# stackable_motorshield_v2.net
KiCad netlist of a schematic drawn in EAGLE
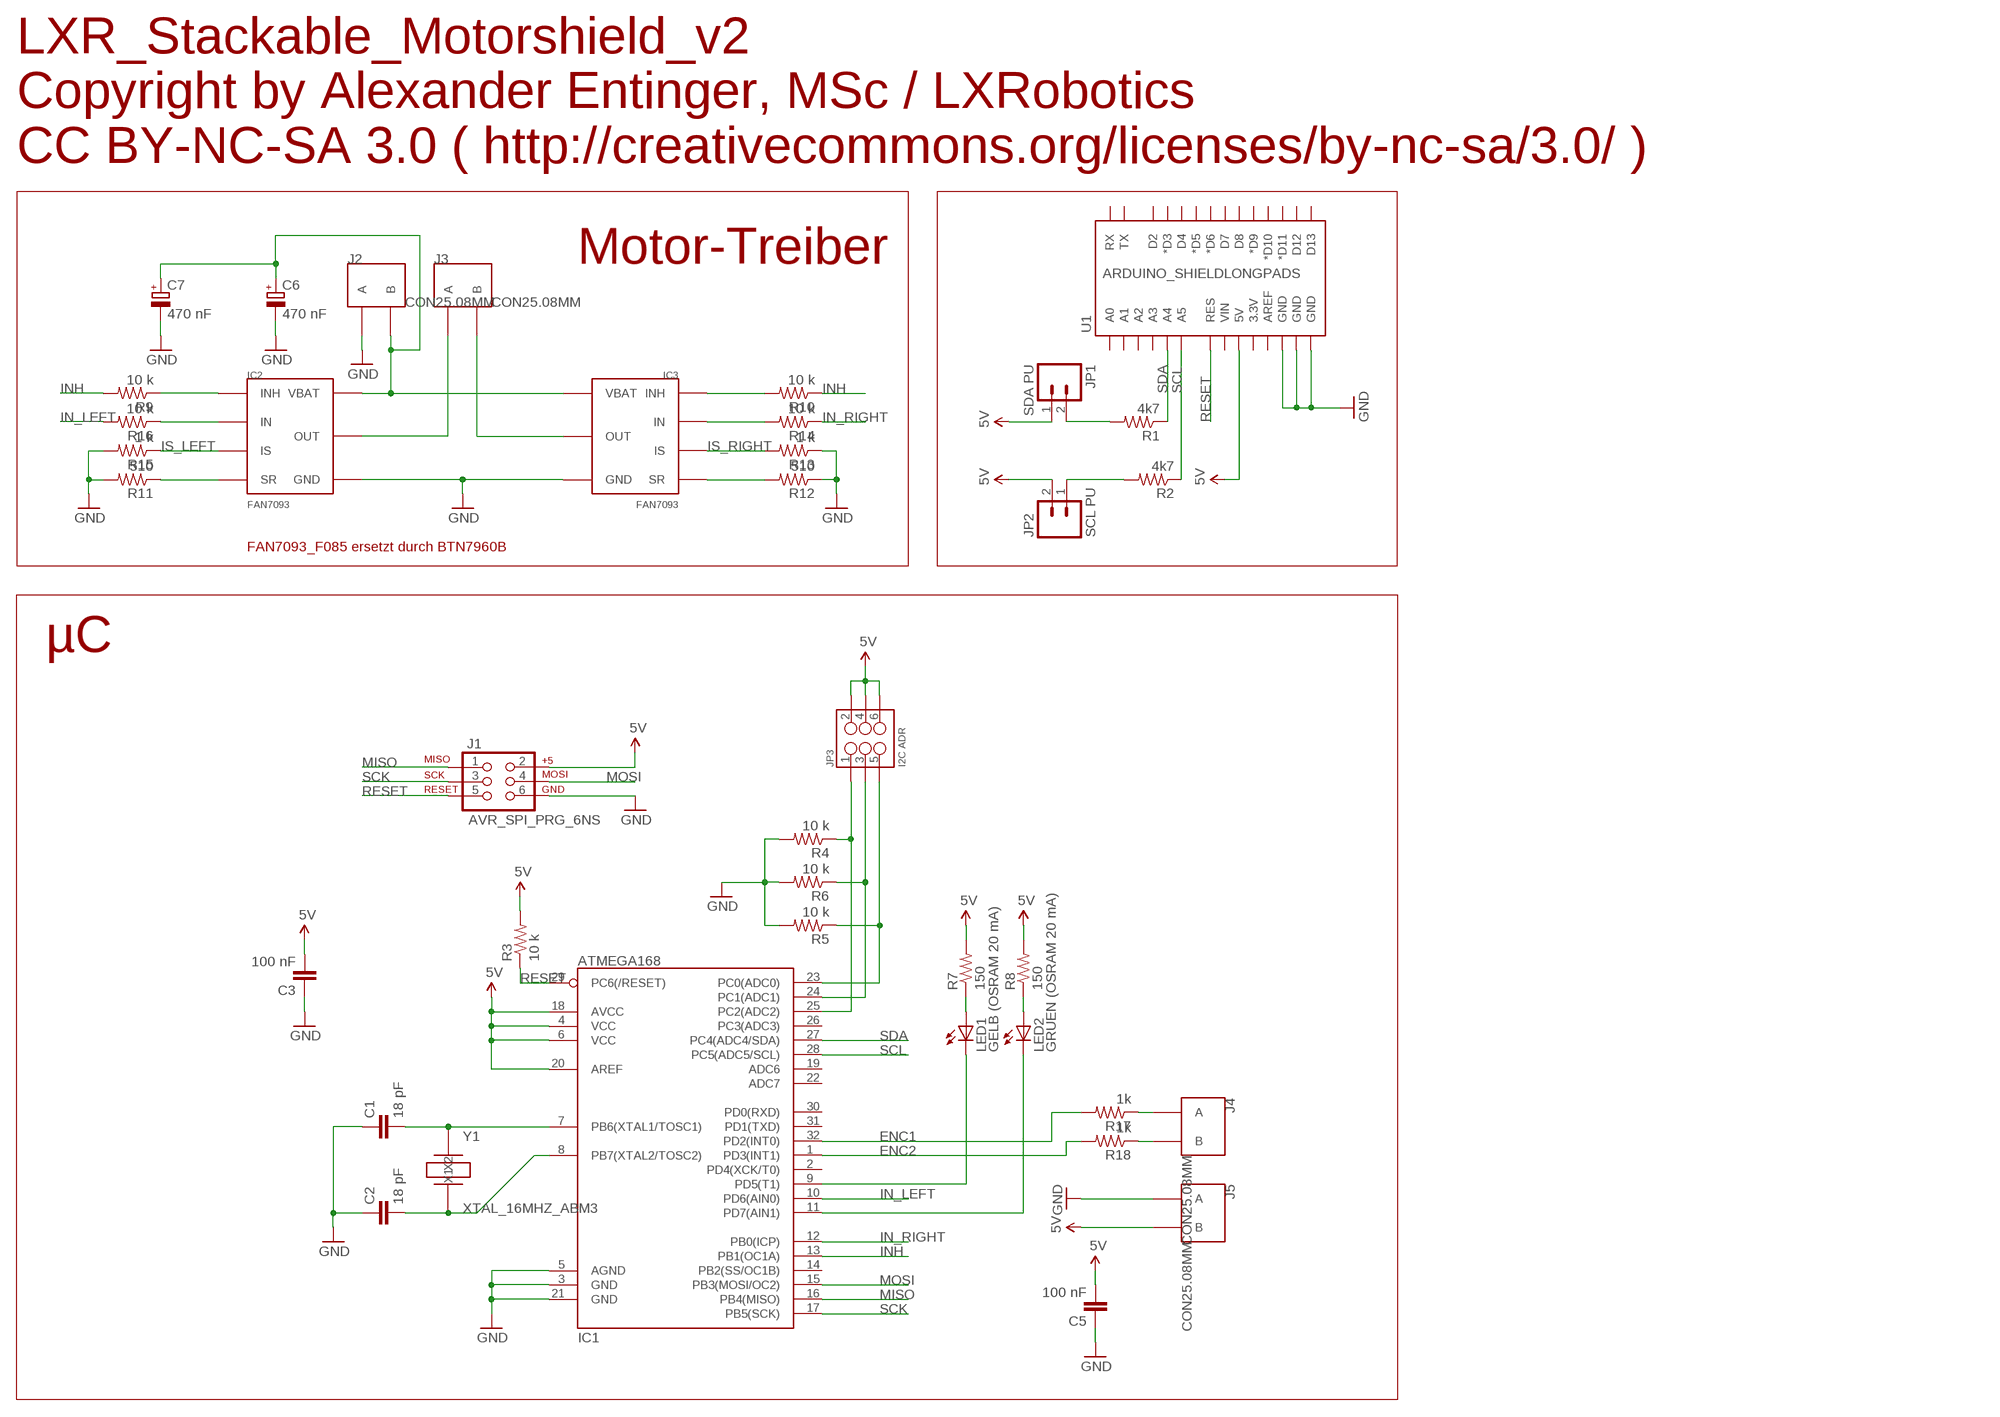
[diagram p0: schematic, sheet 1]

(export (version "E")
  (design (tool "Eeschema 10.0.6"))
  (components
    (comp (ref "C1")
      (value "18 pF")
      (footprint "eagle-import:C0805")
      (libsource (lib "eagle-import") (part "C-EUC0805"))
    )
    (comp (ref "C2")
      (value "18 pF")
      (footprint "eagle-import:C0805")
      (libsource (lib "eagle-import") (part "C-EUC0805"))
    )
    (comp (ref "C3")
      (value "100 nF")
      (footprint "eagle-import:C0805")
      (libsource (lib "eagle-import") (part "C-EUC0805"))
    )
    (comp (ref "C5")
      (value "100 nF")
      (footprint "eagle-import:C0805")
      (libsource (lib "eagle-import") (part "C-EUC0805"))
    )
    (comp (ref "C6")
      (value "470 nF")
      (footprint "eagle-import:KEMET_A")
      (libsource (lib "eagle-import") (part "CPOL-EU"))
    )
    (comp (ref "C7")
      (value "470 nF")
      (footprint "eagle-import:KEMET_A")
      (libsource (lib "eagle-import") (part "CPOL-EU"))
    )
    (comp (ref "IC1")
      (value "ATMEGA168")
      (footprint "eagle-import:TQFP32-08")
      (libsource (lib "eagle-import") (part "ATMEGA168"))
    )
    (comp (ref "IC2")
      (value "FAN7093")
      (footprint "eagle-import:TO263-7L")
      (libsource (lib "eagle-import") (part "FAN7093"))
    )
    (comp (ref "IC3")
      (value "FAN7093")
      (footprint "eagle-import:TO263-7L")
      (libsource (lib "eagle-import") (part "FAN7093"))
    )
    (comp (ref "J1")
      (value "AVR_SPI_PRG_6NS")
      (footprint "eagle-import:2X3-NS")
      (libsource (lib "eagle-import") (part "AVR_SPI_PRG_6NS"))
    )
    (comp (ref "J2")
      (value "CON25.08MM")
      (footprint "eagle-import:CON2_SCHRAUBKLEMME")
      (libsource (lib "eagle-import") (part "CON25.08MM"))
    )
    (comp (ref "J3")
      (value "CON25.08MM")
      (footprint "eagle-import:CON2_SCHRAUBKLEMME")
      (libsource (lib "eagle-import") (part "CON25.08MM"))
    )
    (comp (ref "J4")
      (value "CON25.08MM")
      (footprint "eagle-import:CON2_SCHRAUBKLEMME")
      (libsource (lib "eagle-import") (part "CON25.08MM"))
    )
    (comp (ref "J5")
      (value "CON25.08MM")
      (footprint "eagle-import:CON2_SCHRAUBKLEMME")
      (libsource (lib "eagle-import") (part "CON25.08MM"))
    )
    (comp (ref "JP1")
      (value "SDA PU")
      (footprint "eagle-import:1X02")
      (libsource (lib "eagle-import") (part "M02PTH"))
    )
    (comp (ref "JP2")
      (value "SCL PU")
      (footprint "eagle-import:1X02")
      (libsource (lib "eagle-import") (part "M02PTH"))
    )
    (comp (ref "JP3")
      (value "I2C ADR")
      (footprint "eagle-import:2X3_POGO")
      (libsource (lib "eagle-import") (part "M03X2POGO_PINS"))
    )
    (comp (ref "LED1")
      (value "GELB (OSRAM 20 mA)")
      (footprint "eagle-import:CHIP-LED0805")
      (libsource (lib "eagle-import") (part "LEDCHIP-LED0805"))
    )
    (comp (ref "LED2")
      (value "GRUEN (OSRAM 20 mA)")
      (footprint "eagle-import:CHIP-LED0805")
      (libsource (lib "eagle-import") (part "LEDCHIP-LED0805"))
    )
    (comp (ref "R1")
      (value "4k7")
      (footprint "eagle-import:0805")
      (libsource (lib "eagle-import") (part "RESISTOR0805-RES"))
    )
    (comp (ref "R2")
      (value "4k7")
      (footprint "eagle-import:0805")
      (libsource (lib "eagle-import") (part "RESISTOR0805-RES"))
    )
    (comp (ref "R3")
      (value "10 k")
      (footprint "eagle-import:0805")
      (libsource (lib "eagle-import") (part "RESISTOR0805-RES"))
    )
    (comp (ref "R4")
      (value "10 k")
      (footprint "eagle-import:0805")
      (libsource (lib "eagle-import") (part "RESISTOR0805-RES"))
    )
    (comp (ref "R5")
      (value "10 k")
      (footprint "eagle-import:0805")
      (libsource (lib "eagle-import") (part "RESISTOR0805-RES"))
    )
    (comp (ref "R6")
      (value "10 k")
      (footprint "eagle-import:0805")
      (libsource (lib "eagle-import") (part "RESISTOR0805-RES"))
    )
    (comp (ref "R7")
      (value "150")
      (footprint "eagle-import:0805")
      (libsource (lib "eagle-import") (part "RESISTOR0805-RES"))
    )
    (comp (ref "R8")
      (value "150")
      (footprint "eagle-import:0805")
      (libsource (lib "eagle-import") (part "RESISTOR0805-RES"))
    )
    (comp (ref "R9")
      (value "10 k")
      (footprint "eagle-import:0805")
      (libsource (lib "eagle-import") (part "RESISTOR0805-RES"))
    )
    (comp (ref "R10")
      (value "10 k")
      (footprint "eagle-import:0805")
      (libsource (lib "eagle-import") (part "RESISTOR0805-RES"))
    )
    (comp (ref "R11")
      (value "510")
      (footprint "eagle-import:0805")
      (libsource (lib "eagle-import") (part "RESISTOR0805-RES"))
    )
    (comp (ref "R12")
      (value "510")
      (footprint "eagle-import:0805")
      (libsource (lib "eagle-import") (part "RESISTOR0805-RES"))
    )
    (comp (ref "R13")
      (value "1 k")
      (footprint "eagle-import:0805")
      (libsource (lib "eagle-import") (part "RESISTOR0805-RES"))
    )
    (comp (ref "R14")
      (value "10 k")
      (footprint "eagle-import:0805")
      (libsource (lib "eagle-import") (part "RESISTOR0805-RES"))
    )
    (comp (ref "R15")
      (value "1 k")
      (footprint "eagle-import:0805")
      (libsource (lib "eagle-import") (part "RESISTOR0805-RES"))
    )
    (comp (ref "R16")
      (value "10 k")
      (footprint "eagle-import:0805")
      (libsource (lib "eagle-import") (part "RESISTOR0805-RES"))
    )
    (comp (ref "R17")
      (value "1k")
      (footprint "eagle-import:0805")
      (libsource (lib "eagle-import") (part "RESISTOR0805-RES"))
    )
    (comp (ref "R18")
      (value "1k")
      (footprint "eagle-import:0805")
      (libsource (lib "eagle-import") (part "RESISTOR0805-RES"))
    )
    (comp (ref "U1")
      (value "ARDUINO_SHIELDLONGPADS")
      (footprint "eagle-import:DUEMILANOVE_SHIELD_LONGPADS")
      (libsource (lib "eagle-import") (part "ARDUINO_SHIELDLONGPADS"))
    )
    (comp (ref "Y1")
      (value "XTAL_16MHZ_ABM3")
      (footprint "eagle-import:ABM3")
      (libsource (lib "eagle-import") (part "XTAL_16MHZ_ABM3"))
    )
  )
  (nets
    (net (code "1") (name "/ENC1") (class "Default")
      (node (ref "IC1") (pin "32") (pinfunction "PD2(INT0)_32") (pintype "bidirectional"))
      (node (ref "R17") (pin "2") (pinfunction "2_2") (pintype "passive"))
    )
    (net (code "2") (name "/ENC2") (class "Default")
      (node (ref "IC1") (pin "1") (pinfunction "PD3(INT1)_1") (pintype "bidirectional"))
      (node (ref "R18") (pin "2") (pinfunction "2_2") (pintype "passive"))
    )
    (net (code "3") (name "/INH") (class "Default")
      (node (ref "IC1") (pin "13") (pinfunction "PB1(OC1A)_13") (pintype "bidirectional"))
      (node (ref "R10") (pin "1") (pinfunction "1_1") (pintype "passive"))
      (node (ref "R9") (pin "2") (pinfunction "2_2") (pintype "passive"))
    )
    (net (code "4") (name "/IN_LEFT") (class "Default")
      (node (ref "IC1") (pin "10") (pinfunction "PD6(AIN0)_10") (pintype "bidirectional"))
      (node (ref "R16") (pin "2") (pinfunction "2_2") (pintype "passive"))
    )
    (net (code "5") (name "/IN_RIGHT") (class "Default")
      (node (ref "IC1") (pin "12") (pinfunction "PB0(ICP)_12") (pintype "bidirectional"))
      (node (ref "R14") (pin "1") (pinfunction "1_1") (pintype "passive"))
    )
    (net (code "6") (name "/IS_LEFT") (class "Default")
      (node (ref "IC2") (pin "IS") (pinfunction "IS_IS") (pintype "bidirectional"))
      (node (ref "R15") (pin "1") (pinfunction "1_1") (pintype "passive"))
    )
    (net (code "7") (name "/IS_RIGHT") (class "Default")
      (node (ref "IC3") (pin "IS") (pinfunction "IS_IS") (pintype "bidirectional"))
      (node (ref "R13") (pin "2") (pinfunction "2_2") (pintype "passive"))
    )
    (net (code "8") (name "/MISO") (class "Default")
      (node (ref "IC1") (pin "16") (pinfunction "PB4(MISO)_16") (pintype "bidirectional"))
      (node (ref "J1") (pin "1") (pinfunction "1_1") (pintype "passive"))
    )
    (net (code "9") (name "/MOSI") (class "Default")
      (node (ref "IC1") (pin "15") (pinfunction "PB3(MOSI/OC2)_15") (pintype "bidirectional"))
      (node (ref "J1") (pin "4") (pinfunction "4_4") (pintype "passive"))
    )
    (net (code "10") (name "/RESET") (class "Default")
      (node (ref "IC1") (pin "29") (pinfunction "PC6(/RESET)_29") (pintype "bidirectional"))
      (node (ref "J1") (pin "5") (pinfunction "5_5") (pintype "passive"))
      (node (ref "R3") (pin "1") (pinfunction "1_1") (pintype "passive"))
      (node (ref "U1") (pin "RES") (pinfunction "RES_RES") (pintype "bidirectional"))
    )
    (net (code "11") (name "/SCK") (class "Default")
      (node (ref "IC1") (pin "17") (pinfunction "PB5(SCK)_17") (pintype "bidirectional"))
      (node (ref "J1") (pin "3") (pinfunction "3_3") (pintype "passive"))
    )
    (net (code "12") (name "/SCL") (class "Default")
      (node (ref "IC1") (pin "28") (pinfunction "PC5(ADC5/SCL)_28") (pintype "bidirectional"))
      (node (ref "R2") (pin "1") (pinfunction "1_1") (pintype "passive"))
      (node (ref "U1") (pin "A5") (pinfunction "A5_A5") (pintype "bidirectional"))
    )
    (net (code "13") (name "/SDA") (class "Default")
      (node (ref "IC1") (pin "27") (pinfunction "PC4(ADC4/SDA)_27") (pintype "bidirectional"))
      (node (ref "R1") (pin "1") (pinfunction "1_1") (pintype "passive"))
      (node (ref "U1") (pin "A4") (pinfunction "A4_A4") (pintype "bidirectional"))
    )
    (net (code "14") (name "5V") (class "Default")
      (node (ref "C3") (pin "2") (pinfunction "2_2") (pintype "passive"))
      (node (ref "C5") (pin "2") (pinfunction "2_2") (pintype "passive"))
      (node (ref "IC1") (pin "18") (pinfunction "AVCC_18") (pintype "bidirectional"))
      (node (ref "IC1") (pin "20") (pinfunction "AREF_20") (pintype "bidirectional"))
      (node (ref "IC1") (pin "4") (pinfunction "VCC_4") (pintype "bidirectional"))
      (node (ref "IC1") (pin "6") (pinfunction "VCC_6") (pintype "bidirectional"))
      (node (ref "J1") (pin "2") (pinfunction "2_2") (pintype "passive"))
      (node (ref "J5") (pin "2") (pinfunction "B_2") (pintype "bidirectional"))
      (node (ref "JP1") (pin "1") (pinfunction "1_1") (pintype "passive"))
      (node (ref "JP2") (pin "2") (pinfunction "2_2") (pintype "passive"))
      (node (ref "JP3") (pin "P$2") (pinfunction "2_P$2") (pintype "bidirectional"))
      (node (ref "JP3") (pin "P$4") (pinfunction "4_P$4") (pintype "bidirectional"))
      (node (ref "JP3") (pin "P$6") (pinfunction "6_P$6") (pintype "bidirectional"))
      (node (ref "R3") (pin "2") (pinfunction "2_2") (pintype "passive"))
      (node (ref "R7") (pin "2") (pinfunction "2_2") (pintype "passive"))
      (node (ref "R8") (pin "2") (pinfunction "2_2") (pintype "passive"))
      (node (ref "U1") (pin "5V") (pinfunction "5V_5V") (pintype "bidirectional"))
    )
    (net (code "15") (name "GND") (class "Default")
      (node (ref "C1") (pin "1") (pinfunction "1_1") (pintype "passive"))
      (node (ref "C2") (pin "1") (pinfunction "1_1") (pintype "passive"))
      (node (ref "C3") (pin "1") (pinfunction "1_1") (pintype "passive"))
      (node (ref "C5") (pin "1") (pinfunction "1_1") (pintype "passive"))
      (node (ref "C6") (pin "CATHODE") (pinfunction "-_CATHODE") (pintype "passive"))
      (node (ref "C7") (pin "CATHODE") (pinfunction "-_CATHODE") (pintype "passive"))
      (node (ref "IC1") (pin "21") (pinfunction "GND_21") (pintype "bidirectional"))
      (node (ref "IC1") (pin "3") (pinfunction "GND_3") (pintype "bidirectional"))
      (node (ref "IC1") (pin "5") (pinfunction "AGND_5") (pintype "bidirectional"))
      (node (ref "IC2") (pin "GND") (pinfunction "GND_GND") (pintype "bidirectional"))
      (node (ref "IC3") (pin "GND") (pinfunction "GND_GND") (pintype "bidirectional"))
      (node (ref "J1") (pin "6") (pinfunction "6_6") (pintype "passive"))
      (node (ref "J2") (pin "1") (pinfunction "A_1") (pintype "bidirectional"))
      (node (ref "J5") (pin "1") (pinfunction "A_1") (pintype "bidirectional"))
      (node (ref "R11") (pin "2") (pinfunction "2_2") (pintype "passive"))
      (node (ref "R12") (pin "1") (pinfunction "1_1") (pintype "passive"))
      (node (ref "R13") (pin "1") (pinfunction "1_1") (pintype "passive"))
      (node (ref "R15") (pin "2") (pinfunction "2_2") (pintype "passive"))
      (node (ref "R4") (pin "2") (pinfunction "2_2") (pintype "passive"))
      (node (ref "R5") (pin "2") (pinfunction "2_2") (pintype "passive"))
      (node (ref "R6") (pin "2") (pinfunction "2_2") (pintype "passive"))
      (node (ref "U1") (pin "GND@0") (pinfunction "GND_GND@0") (pintype "bidirectional"))
      (node (ref "U1") (pin "GND@1") (pinfunction "GND_GND@1") (pintype "bidirectional"))
      (node (ref "U1") (pin "GND@2") (pinfunction "GND_GND@2") (pintype "bidirectional"))
    )
    (net (code "16") (name "Net-(C6-+)") (class "Default")
      (node (ref "C6") (pin "ANODE") (pinfunction "+_ANODE") (pintype "passive"))
      (node (ref "C7") (pin "ANODE") (pinfunction "+_ANODE") (pintype "passive"))
      (node (ref "IC2") (pin "VBATT") (pinfunction "VBAT_VBATT") (pintype "bidirectional"))
      (node (ref "IC3") (pin "VBATT") (pinfunction "VBAT_VBATT") (pintype "bidirectional"))
      (node (ref "J2") (pin "2") (pinfunction "B_2") (pintype "bidirectional"))
    )
    (net (code "17") (name "Net-(IC1-PB6(XTAL1{slash}TOSC1))") (class "Default")
      (node (ref "C1") (pin "2") (pinfunction "2_2") (pintype "passive"))
      (node (ref "IC1") (pin "7") (pinfunction "PB6(XTAL1/TOSC1)_7") (pintype "bidirectional"))
      (node (ref "Y1") (pin "X1") (pinfunction "X1_X1") (pintype "bidirectional"))
    )
    (net (code "18") (name "Net-(IC1-PB7(XTAL2{slash}TOSC2))") (class "Default")
      (node (ref "C2") (pin "2") (pinfunction "2_2") (pintype "passive"))
      (node (ref "IC1") (pin "8") (pinfunction "PB7(XTAL2/TOSC2)_8") (pintype "bidirectional"))
      (node (ref "Y1") (pin "X2") (pinfunction "X2_X2") (pintype "bidirectional"))
    )
    (net (code "19") (name "Net-(IC1-PC0(ADC0))") (class "Default")
      (node (ref "IC1") (pin "23") (pinfunction "PC0(ADC0)_23") (pintype "bidirectional"))
      (node (ref "JP3") (pin "P$5") (pinfunction "5_P$5") (pintype "bidirectional"))
      (node (ref "R5") (pin "1") (pinfunction "1_1") (pintype "passive"))
    )
    (net (code "20") (name "Net-(IC1-PC1(ADC1))") (class "Default")
      (node (ref "IC1") (pin "24") (pinfunction "PC1(ADC1)_24") (pintype "bidirectional"))
      (node (ref "JP3") (pin "P$3") (pinfunction "3_P$3") (pintype "bidirectional"))
      (node (ref "R6") (pin "1") (pinfunction "1_1") (pintype "passive"))
    )
    (net (code "21") (name "Net-(IC1-PC2(ADC2))") (class "Default")
      (node (ref "IC1") (pin "25") (pinfunction "PC2(ADC2)_25") (pintype "bidirectional"))
      (node (ref "JP3") (pin "P$1") (pinfunction "1_P$1") (pintype "bidirectional"))
      (node (ref "R4") (pin "1") (pinfunction "1_1") (pintype "passive"))
    )
    (net (code "22") (name "Net-(IC1-PD5(T1))") (class "Default")
      (node (ref "IC1") (pin "9") (pinfunction "PD5(T1)_9") (pintype "bidirectional"))
      (node (ref "LED1") (pin "C") (pinfunction "C_C") (pintype "passive"))
    )
    (net (code "23") (name "Net-(IC1-PD7(AIN1))") (class "Default")
      (node (ref "IC1") (pin "11") (pinfunction "PD7(AIN1)_11") (pintype "bidirectional"))
      (node (ref "LED2") (pin "C") (pinfunction "C_C") (pintype "passive"))
    )
    (net (code "24") (name "Net-(IC2-PadIN)") (class "Default")
      (node (ref "IC2") (pin "IN") (pinfunction "IN_IN") (pintype "bidirectional"))
      (node (ref "R16") (pin "1") (pinfunction "1_1") (pintype "passive"))
    )
    (net (code "25") (name "Net-(IC2-PadINH)") (class "Default")
      (node (ref "IC2") (pin "INH") (pinfunction "INH_INH") (pintype "bidirectional"))
      (node (ref "R9") (pin "1") (pinfunction "1_1") (pintype "passive"))
    )
    (net (code "26") (name "Net-(IC2-PadSR)") (class "Default")
      (node (ref "IC2") (pin "SR") (pinfunction "SR_SR") (pintype "bidirectional"))
      (node (ref "R11") (pin "1") (pinfunction "1_1") (pintype "passive"))
    )
    (net (code "27") (name "Net-(IC3-PadIN)") (class "Default")
      (node (ref "IC3") (pin "IN") (pinfunction "IN_IN") (pintype "bidirectional"))
      (node (ref "R14") (pin "2") (pinfunction "2_2") (pintype "passive"))
    )
    (net (code "28") (name "Net-(IC3-PadINH)") (class "Default")
      (node (ref "IC3") (pin "INH") (pinfunction "INH_INH") (pintype "bidirectional"))
      (node (ref "R10") (pin "2") (pinfunction "2_2") (pintype "passive"))
    )
    (net (code "29") (name "Net-(IC3-PadSR)") (class "Default")
      (node (ref "IC3") (pin "SR") (pinfunction "SR_SR") (pintype "bidirectional"))
      (node (ref "R12") (pin "2") (pinfunction "2_2") (pintype "passive"))
    )
    (net (code "30") (name "Net-(J3-A)") (class "Default")
      (node (ref "IC2") (pin "OUT") (pinfunction "OUT_OUT") (pintype "bidirectional"))
      (node (ref "IC2") (pin "OUT@1") (pinfunction "OUT_OUT@1") (pintype "bidirectional"))
      (node (ref "J3") (pin "1") (pinfunction "A_1") (pintype "bidirectional"))
    )
    (net (code "31") (name "Net-(J3-B)") (class "Default")
      (node (ref "IC3") (pin "OUT") (pinfunction "OUT_OUT") (pintype "bidirectional"))
      (node (ref "IC3") (pin "OUT@1") (pinfunction "OUT_OUT@1") (pintype "bidirectional"))
      (node (ref "J3") (pin "2") (pinfunction "B_2") (pintype "bidirectional"))
    )
    (net (code "32") (name "Net-(J4-A)") (class "Default")
      (node (ref "J4") (pin "1") (pinfunction "A_1") (pintype "bidirectional"))
      (node (ref "R17") (pin "1") (pinfunction "1_1") (pintype "passive"))
    )
    (net (code "33") (name "Net-(J4-B)") (class "Default")
      (node (ref "J4") (pin "2") (pinfunction "B_2") (pintype "bidirectional"))
      (node (ref "R18") (pin "1") (pinfunction "1_1") (pintype "passive"))
    )
    (net (code "34") (name "Net-(JP1-Pad2)") (class "Default")
      (node (ref "JP1") (pin "2") (pinfunction "2_2") (pintype "passive"))
      (node (ref "R1") (pin "2") (pinfunction "2_2") (pintype "passive"))
    )
    (net (code "35") (name "Net-(JP2-Pad1)") (class "Default")
      (node (ref "JP2") (pin "1") (pinfunction "1_1") (pintype "passive"))
      (node (ref "R2") (pin "2") (pinfunction "2_2") (pintype "passive"))
    )
    (net (code "36") (name "Net-(LED1-PadA)") (class "Default")
      (node (ref "LED1") (pin "A") (pinfunction "A_A") (pintype "passive"))
      (node (ref "R7") (pin "1") (pinfunction "1_1") (pintype "passive"))
    )
    (net (code "37") (name "Net-(LED2-PadA)") (class "Default")
      (node (ref "LED2") (pin "A") (pinfunction "A_A") (pintype "passive"))
      (node (ref "R8") (pin "1") (pinfunction "1_1") (pintype "passive"))
    )
    (net (code "38") (name "unconnected-(IC1-ADC6-Pad19)") (class "Default")
      (node (ref "IC1") (pin "19") (pinfunction "ADC6_19") (pintype "bidirectional"))
    )
    (net (code "39") (name "unconnected-(IC1-ADC7-Pad22)") (class "Default")
      (node (ref "IC1") (pin "22") (pinfunction "ADC7_22") (pintype "bidirectional"))
    )
    (net (code "40") (name "unconnected-(IC1-PB2(SS{slash}OC1B)-Pad14)") (class "Default")
      (node (ref "IC1") (pin "14") (pinfunction "PB2(SS/OC1B)_14") (pintype "bidirectional"))
    )
    (net (code "41") (name "unconnected-(IC1-PC3(ADC3)-Pad26)") (class "Default")
      (node (ref "IC1") (pin "26") (pinfunction "PC3(ADC3)_26") (pintype "bidirectional"))
    )
    (net (code "42") (name "unconnected-(IC1-PD0(RXD)-Pad30)") (class "Default")
      (node (ref "IC1") (pin "30") (pinfunction "PD0(RXD)_30") (pintype "bidirectional"))
    )
    (net (code "43") (name "unconnected-(IC1-PD1(TXD)-Pad31)") (class "Default")
      (node (ref "IC1") (pin "31") (pinfunction "PD1(TXD)_31") (pintype "bidirectional"))
    )
    (net (code "44") (name "unconnected-(IC1-PD4(XCK{slash}T0)-Pad2)") (class "Default")
      (node (ref "IC1") (pin "2") (pinfunction "PD4(XCK/T0)_2") (pintype "bidirectional"))
    )
    (net (code "45") (name "unconnected-(U1-*D3-PadD3)") (class "Default")
      (node (ref "U1") (pin "D3") (pinfunction "*D3_D3") (pintype "bidirectional"))
    )
    (net (code "46") (name "unconnected-(U1-*D5-PadD5)") (class "Default")
      (node (ref "U1") (pin "D5") (pinfunction "*D5_D5") (pintype "bidirectional"))
    )
    (net (code "47") (name "unconnected-(U1-*D6-PadD6)") (class "Default")
      (node (ref "U1") (pin "D6") (pinfunction "*D6_D6") (pintype "bidirectional"))
    )
    (net (code "48") (name "unconnected-(U1-*D9-PadD9)") (class "Default")
      (node (ref "U1") (pin "D9") (pinfunction "*D9_D9") (pintype "bidirectional"))
    )
    (net (code "49") (name "unconnected-(U1-*D10-PadD10)") (class "Default")
      (node (ref "U1") (pin "D10") (pinfunction "*D10_D10") (pintype "bidirectional"))
    )
    (net (code "50") (name "unconnected-(U1-*D11-PadD11)") (class "Default")
      (node (ref "U1") (pin "D11") (pinfunction "*D11_D11") (pintype "bidirectional"))
    )
    (net (code "51") (name "unconnected-(U1-Pad3.3V)") (class "Default")
      (node (ref "U1") (pin "3.3V") (pinfunction "3.3V_3.3V") (pintype "bidirectional"))
    )
    (net (code "52") (name "unconnected-(U1-PadA0)") (class "Default")
      (node (ref "U1") (pin "A0") (pinfunction "A0_A0") (pintype "bidirectional"))
    )
    (net (code "53") (name "unconnected-(U1-PadA1)") (class "Default")
      (node (ref "U1") (pin "A1") (pinfunction "A1_A1") (pintype "bidirectional"))
    )
    (net (code "54") (name "unconnected-(U1-PadA2)") (class "Default")
      (node (ref "U1") (pin "A2") (pinfunction "A2_A2") (pintype "bidirectional"))
    )
    (net (code "55") (name "unconnected-(U1-PadA3)") (class "Default")
      (node (ref "U1") (pin "A3") (pinfunction "A3_A3") (pintype "bidirectional"))
    )
    (net (code "56") (name "unconnected-(U1-PadAREF)") (class "Default")
      (node (ref "U1") (pin "AREF") (pinfunction "AREF_AREF") (pintype "bidirectional"))
    )
    (net (code "57") (name "unconnected-(U1-PadD2)") (class "Default")
      (node (ref "U1") (pin "D2") (pinfunction "D2_D2") (pintype "bidirectional"))
    )
    (net (code "58") (name "unconnected-(U1-PadD4)") (class "Default")
      (node (ref "U1") (pin "D4") (pinfunction "D4_D4") (pintype "bidirectional"))
    )
    (net (code "59") (name "unconnected-(U1-PadD7)") (class "Default")
      (node (ref "U1") (pin "D7") (pinfunction "D7_D7") (pintype "bidirectional"))
    )
    (net (code "60") (name "unconnected-(U1-PadD8)") (class "Default")
      (node (ref "U1") (pin "D8") (pinfunction "D8_D8") (pintype "bidirectional"))
    )
    (net (code "61") (name "unconnected-(U1-PadD12)") (class "Default")
      (node (ref "U1") (pin "D12") (pinfunction "D12_D12") (pintype "bidirectional"))
    )
    (net (code "62") (name "unconnected-(U1-PadD13)") (class "Default")
      (node (ref "U1") (pin "D13") (pinfunction "D13_D13") (pintype "bidirectional"))
    )
    (net (code "63") (name "unconnected-(U1-PadRX)") (class "Default")
      (node (ref "U1") (pin "RX") (pinfunction "RX_RX") (pintype "bidirectional"))
    )
    (net (code "64") (name "unconnected-(U1-PadTX)") (class "Default")
      (node (ref "U1") (pin "TX") (pinfunction "TX_TX") (pintype "bidirectional"))
    )
    (net (code "65") (name "unconnected-(U1-PadVIN)") (class "Default")
      (node (ref "U1") (pin "VIN") (pinfunction "VIN_VIN") (pintype "bidirectional"))
    )
  )
)
